# QCopterFC_KEY_Sch.net
KiCad netlist of a schematic drawn in Altium Designer
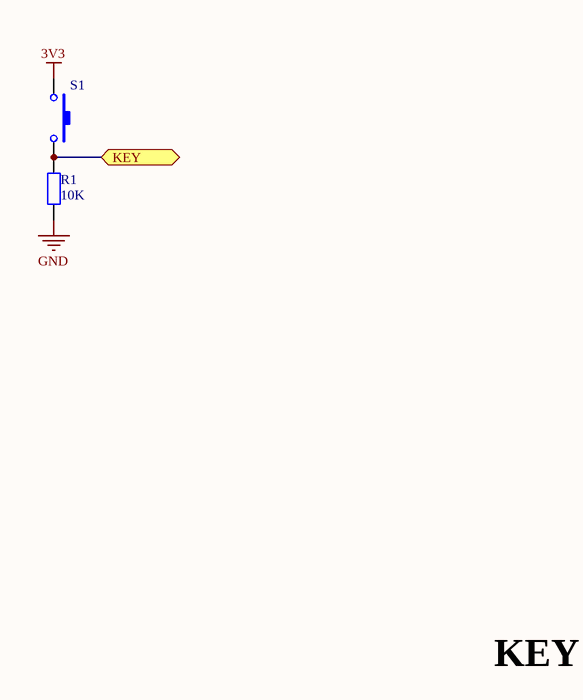
[diagram p0: QCopterFC_KEY_Sch.SchDoc]

(export (version "E")
  (design (tool "Eeschema 10.0.6"))
  (components
    (comp (ref "R1")
      (value "10K")
      (footprint "PCB_Passive:RES_0603")
      (description "Resistor")
      (fields (field (name "Comment") "Res_0603"))
      (libsource (lib "SCH_Passive") (part "Res_0603"))
    )
    (comp (ref "S1")
      (value "SW-PB_1")
      (footprint "PCB_Switch:BT_90_T")
      (description "Switch")
      (fields (field (name "PUBLISHER") "Altium Limited"))
      (libsource (lib "SCH_Switch") (part "SW-PB_1"))
    )
  )
  (nets
    (net (code "1") (name "/KEY") (class "Default")
      (node (ref "R1") (pin "2") (pinfunction "2_2") (pintype "passive"))
      (node (ref "S1") (pin "2") (pinfunction "2_2") (pintype "passive"))
    )
    (net (code "2") (name "3V3") (class "Default")
      (node (ref "S1") (pin "1") (pinfunction "1_1") (pintype "passive"))
    )
    (net (code "3") (name "GND") (class "Default")
      (node (ref "R1") (pin "1") (pinfunction "1_1") (pintype "passive"))
    )
  )
)
